# HW1_28.net
KiCad netlist of a schematic drawn in EasyEDA
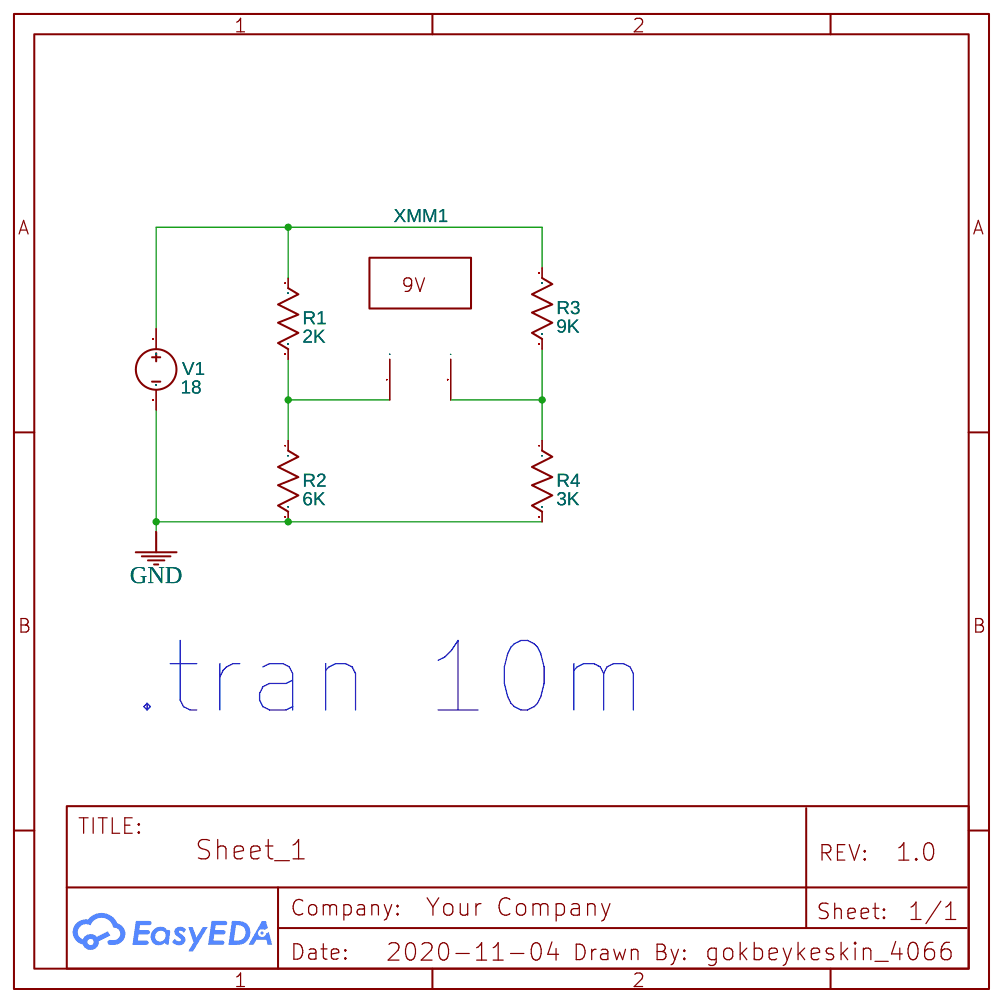
[diagram p0: schematic sheet]

(export (version "E")
  (design (tool "Eeschema 10.0.6"))
  (components
    (comp (ref "R1") (value "2K") (libsource (lib "") (part "Resistor_US")))
    (comp (ref "R2") (value "6K") (libsource (lib "") (part "Resistor_US")))
    (comp (ref "R3") (value "9K") (libsource (lib "") (part "Resistor_US")))
    (comp (ref "R4") (value "3K") (libsource (lib "") (part "Resistor_US")))
    (comp (ref "V1") (value "18") (libsource (lib "") (part "VDC")))
    (comp (ref "XMM1") (value "Multimeter") (libsource (lib "") (part "MULTIMETER")))
  )
  (nets
    (net (code "1") (name "GND") (class "Default")
      (node (ref "R2") (pin "2") (pinfunction "2_2") (pintype "unspecified"))
      (node (ref "R4") (pin "2") (pinfunction "2_2") (pintype "unspecified"))
      (node (ref "V1") (pin "2") (pinfunction "2_2") (pintype "unspecified"))
    )
    (net (code "2") (name "Net-(R1-Pad1)") (class "Default")
      (node (ref "R1") (pin "1") (pinfunction "1_1") (pintype "unspecified"))
      (node (ref "R3") (pin "1") (pinfunction "1_1") (pintype "unspecified"))
      (node (ref "V1") (pin "1") (pinfunction "1_1") (pintype "unspecified"))
    )
    (net (code "3") (name "Net-(XMM1-+)") (class "Default")
      (node (ref "R1") (pin "2") (pinfunction "2_2") (pintype "unspecified"))
      (node (ref "R2") (pin "1") (pinfunction "1_1") (pintype "unspecified"))
      (node (ref "XMM1") (pin "1") (pinfunction "+_1") (pintype "unspecified"))
    )
    (net (code "4") (name "Net-(XMM1-I)") (class "Default")
      (node (ref "R3") (pin "2") (pinfunction "2_2") (pintype "unspecified"))
      (node (ref "R4") (pin "1") (pinfunction "1_1") (pintype "unspecified"))
      (node (ref "XMM1") (pin "2") (pinfunction "I_2") (pintype "unspecified"))
    )
  )
)
